# WMC.net
KiCad netlist of a schematic drawn in EAGLE
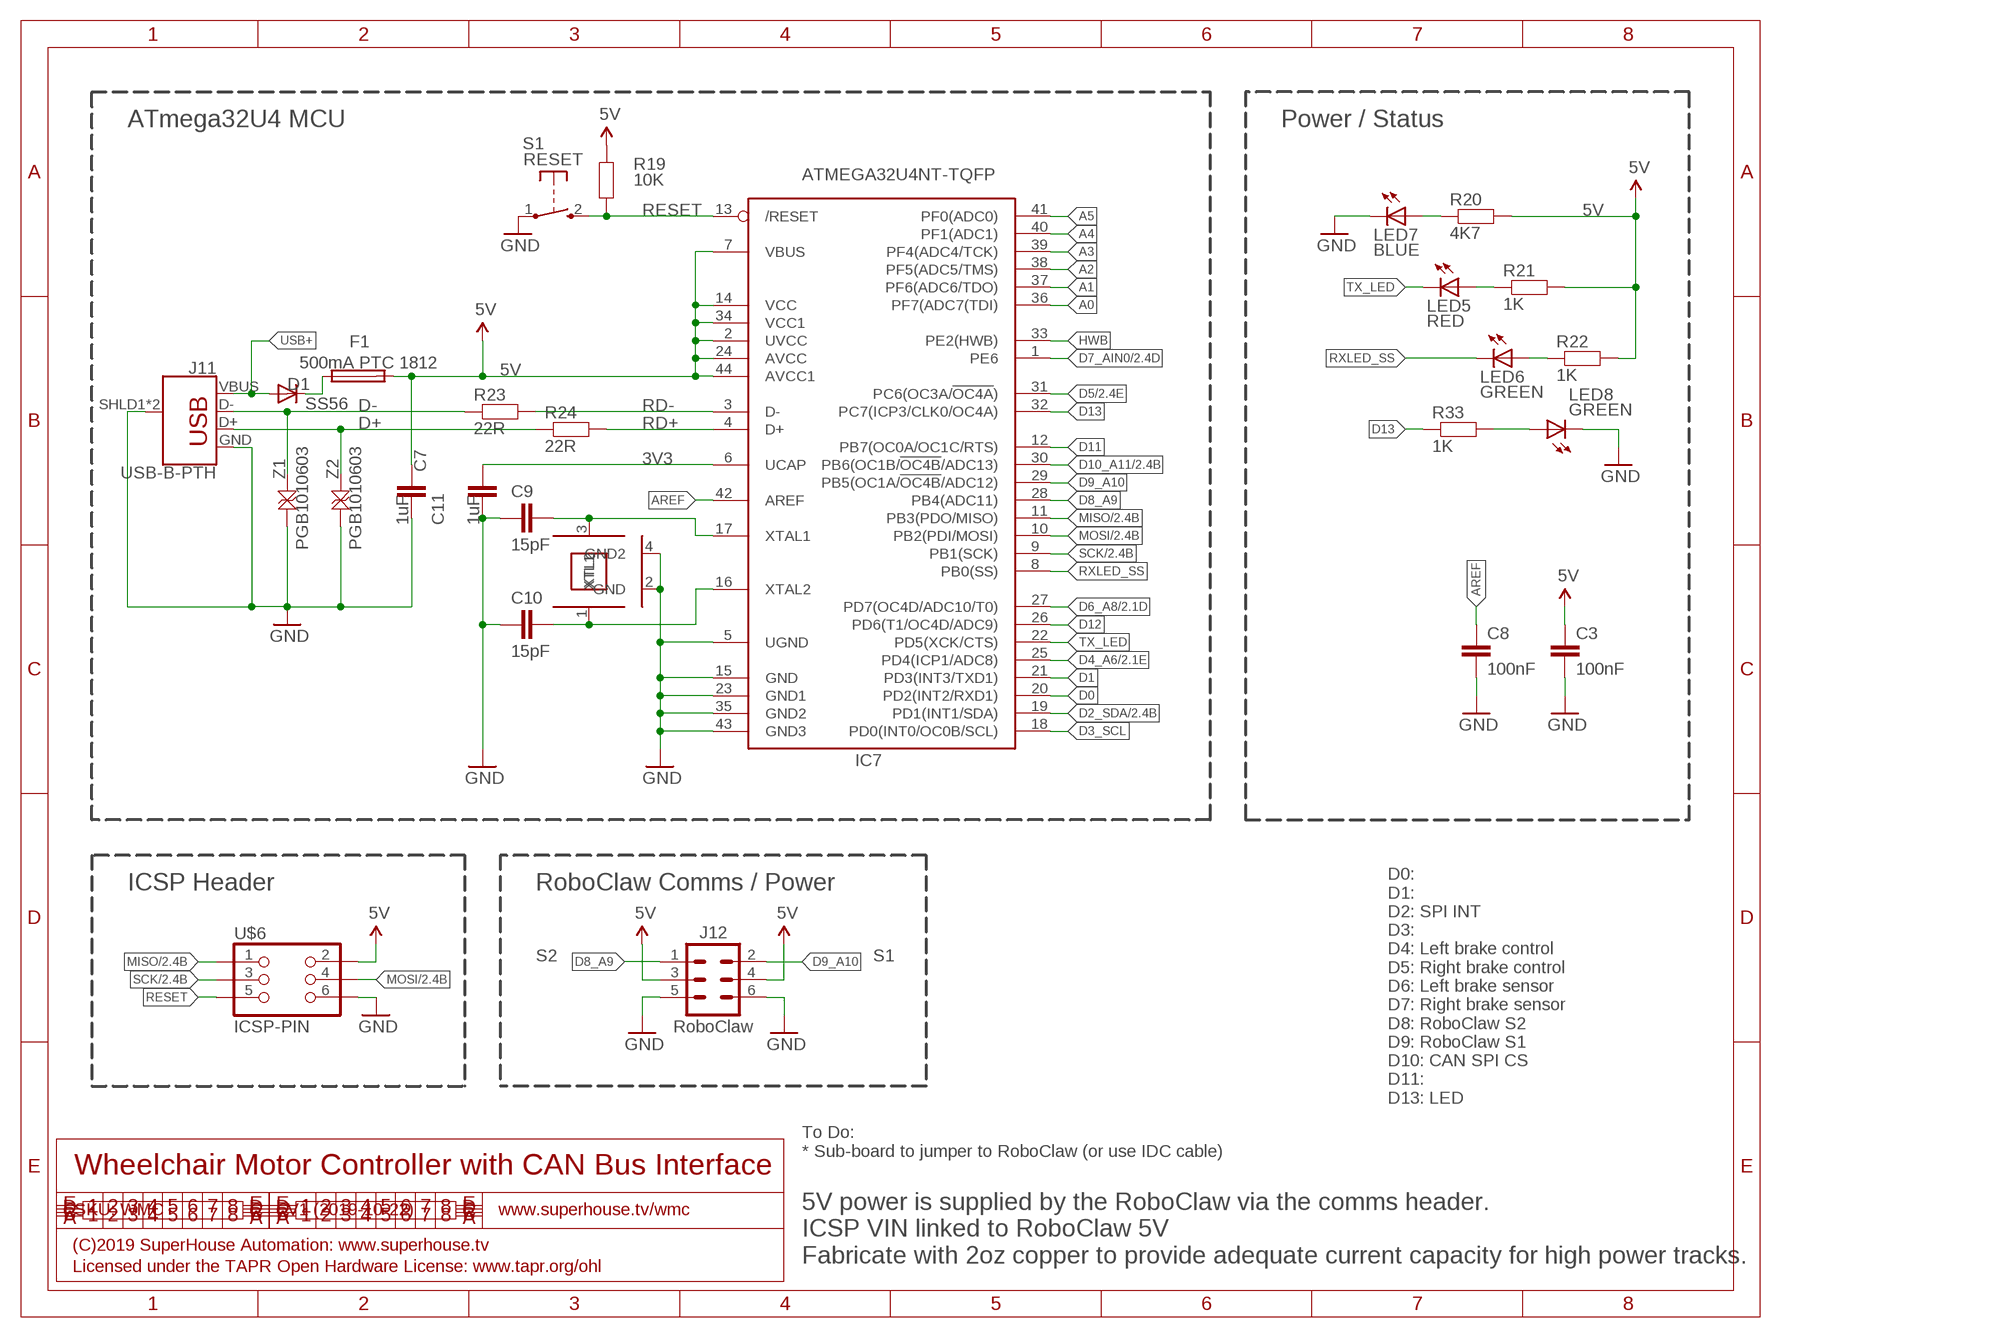
[diagram p0: schematic, sheet 1]
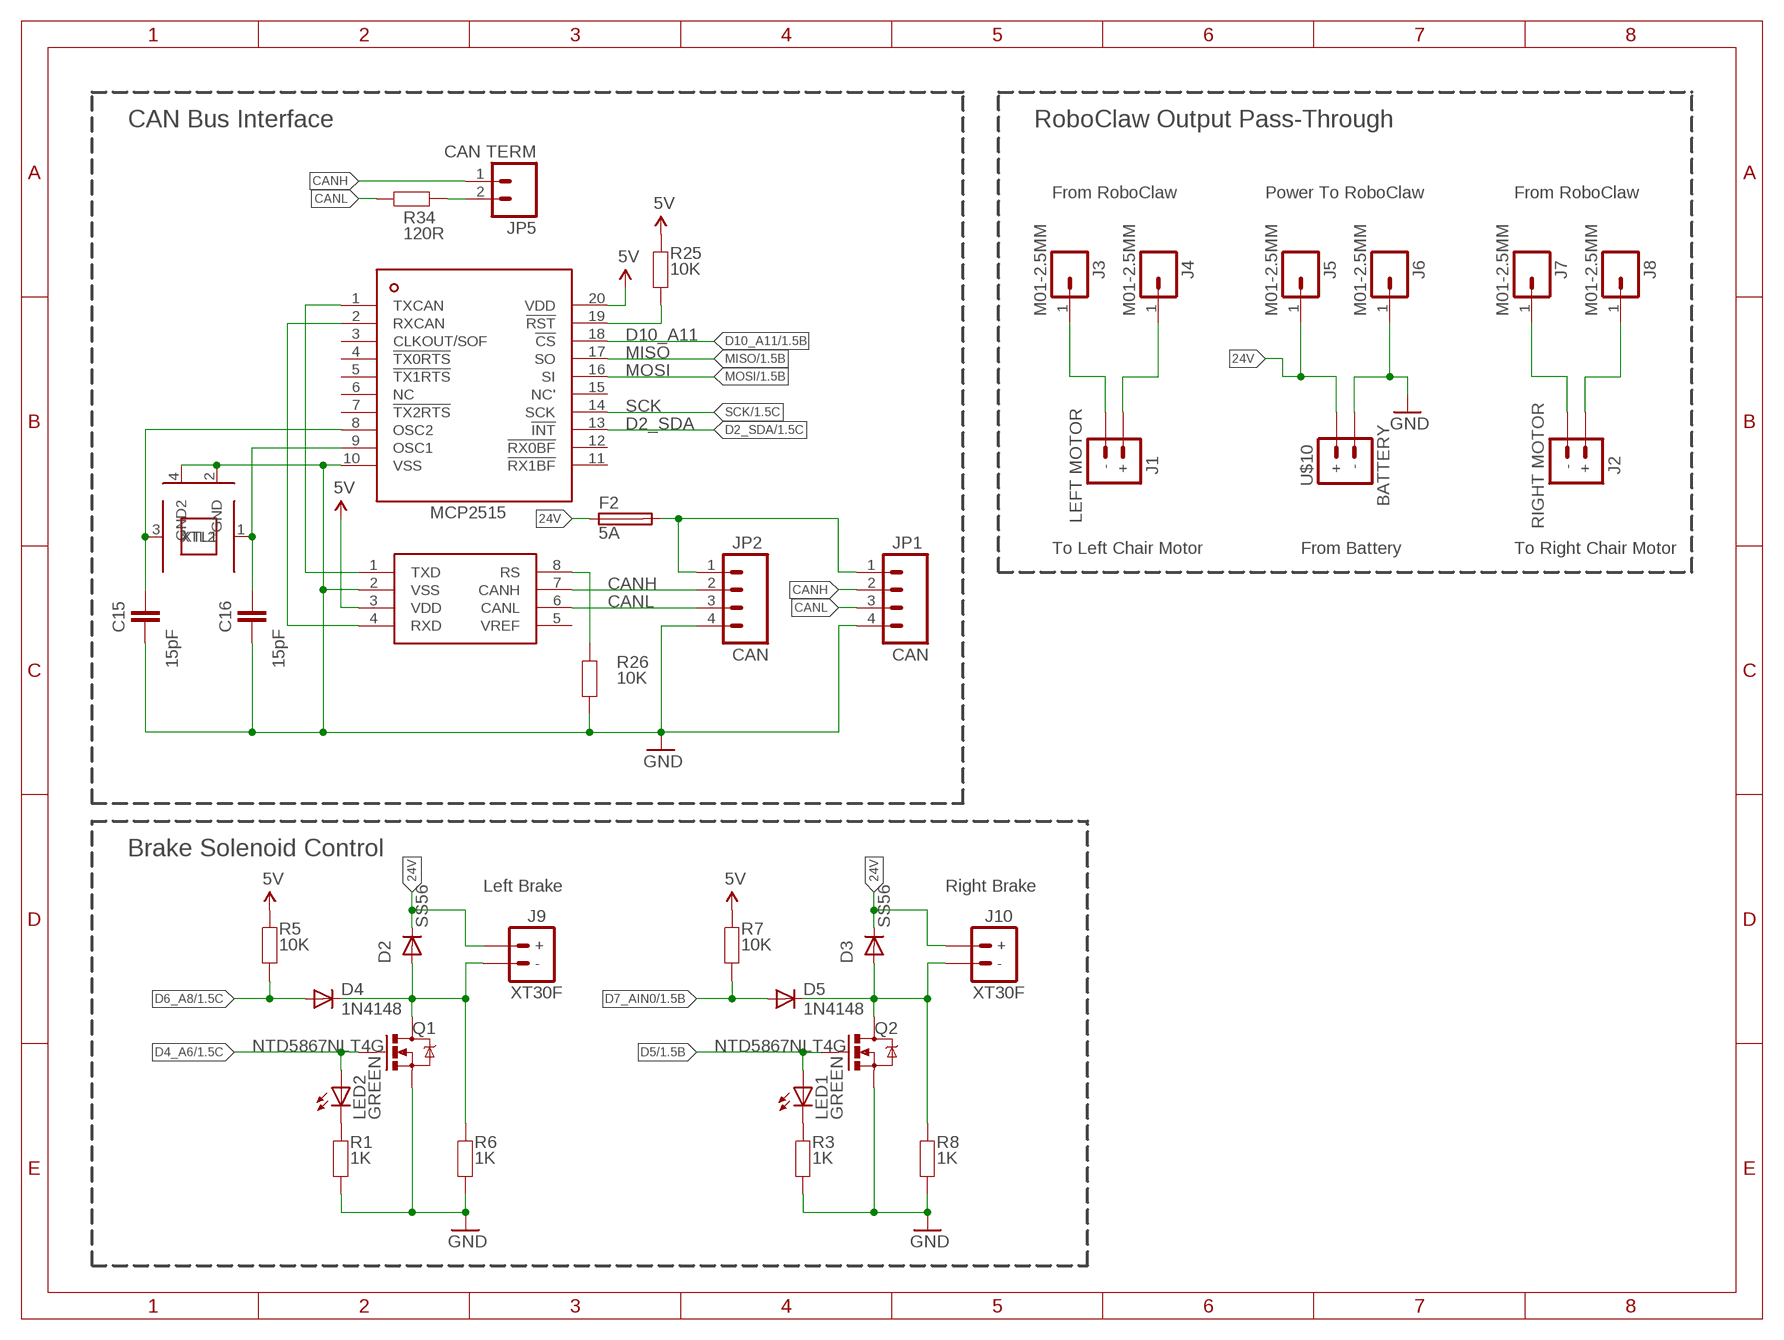
[diagram p1: schematic, sheet 2]

(export (version "E")
  (design (tool "Eeschema 10.0.6"))
  (components
    (comp (ref "C3")
      (value "100nF")
      (footprint "eagle-import:C0603")
      (libsource (lib "eagle-import") (part "CAP0603"))
    )
    (comp (ref "C7")
      (value "1uF")
      (footprint "eagle-import:C0603")
      (libsource (lib "eagle-import") (part "CAP0603"))
    )
    (comp (ref "C8")
      (value "100nF")
      (footprint "eagle-import:C0603")
      (libsource (lib "eagle-import") (part "CAP0603"))
    )
    (comp (ref "C9")
      (value "15pF")
      (footprint "eagle-import:C0603")
      (libsource (lib "eagle-import") (part "CAP0603"))
    )
    (comp (ref "C10")
      (value "15pF")
      (footprint "eagle-import:C0603")
      (libsource (lib "eagle-import") (part "CAP0603"))
    )
    (comp (ref "C11")
      (value "1uF")
      (footprint "eagle-import:C0603")
      (libsource (lib "eagle-import") (part "CAP0603"))
    )
    (comp (ref "D1")
      (value "SS56")
      (footprint "eagle-import:SMA-DIODE")
      (libsource (lib "eagle-import") (part "DIODESMA"))
    )
    (comp (ref "F1")
      (value "500mA PTC 1812")
      (footprint "eagle-import:1812")
      (libsource (lib "eagle-import") (part "PTC050"))
    )
    (comp (ref "IC7")
      (value "ATMEGA32U4NT-TQFP")
      (footprint "eagle-import:TQFP44")
      (libsource (lib "eagle-import") (part "ATMEGA32U4NT-TQFP"))
    )
    (comp (ref "J11")
      (value "USB-B-PTH")
      (footprint "eagle-import:USB-B-PTH")
      (libsource (lib "eagle-import") (part "USB-B-PTH"))
    )
    (comp (ref "J12")
      (value "RoboClaw")
      (footprint "eagle-import:2X03-P")
      (libsource (lib "eagle-import") (part "M02X3-PIN"))
    )
    (comp (ref "LED5")
      (value "RED")
      (footprint "eagle-import:LED-0603")
      (libsource (lib "eagle-import") (part "LED0603"))
    )
    (comp (ref "LED6")
      (value "GREEN")
      (footprint "eagle-import:LED-0603")
      (libsource (lib "eagle-import") (part "LED0603"))
    )
    (comp (ref "LED7")
      (value "BLUE")
      (footprint "eagle-import:LED-0603")
      (libsource (lib "eagle-import") (part "LED0603"))
    )
    (comp (ref "LED8")
      (value "GREEN")
      (footprint "eagle-import:LED-0603")
      (libsource (lib "eagle-import") (part "LED0603"))
    )
    (comp (ref "R19")
      (value "10K")
      (footprint "eagle-import:R0603")
      (libsource (lib "eagle-import") (part "RESISTOR0603"))
    )
    (comp (ref "R20")
      (value "4K7")
      (footprint "eagle-import:R0603")
      (libsource (lib "eagle-import") (part "RESISTOR0603"))
    )
    (comp (ref "R21")
      (value "1K")
      (footprint "eagle-import:R0603")
      (libsource (lib "eagle-import") (part "RESISTOR0603"))
    )
    (comp (ref "R22")
      (value "1K")
      (footprint "eagle-import:R0603")
      (libsource (lib "eagle-import") (part "RESISTOR0603"))
    )
    (comp (ref "R23")
      (value "22R")
      (footprint "eagle-import:R0603")
      (libsource (lib "eagle-import") (part "RESISTOR0603"))
    )
    (comp (ref "R24")
      (value "22R")
      (footprint "eagle-import:R0603")
      (libsource (lib "eagle-import") (part "RESISTOR0603"))
    )
    (comp (ref "R33")
      (value "1K")
      (footprint "eagle-import:R0603")
      (libsource (lib "eagle-import") (part "RESISTOR0603"))
    )
    (comp (ref "S1")
      (value "RESET")
      (footprint "eagle-import:TACTILE_SMT_3X4X2")
      (libsource (lib "eagle-import") (part "TAC_SWITCH_2PINSMT"))
    )
    (comp (ref "U$6")
      (value "ICSP-PIN")
      (footprint "eagle-import:2X03-ICSP")
      (libsource (lib "eagle-import") (part "ICSP-PIN"))
    )
    (comp (ref "XTL2")
      (value "16MHz")
      (footprint "eagle-import:CRYSTAL-SMD-3X2")
      (libsource (lib "eagle-import") (part "CRYSTAL-GND3X2"))
    )
    (comp (ref "Z1")
      (value "PGB1010603")
      (footprint "eagle-import:TVS0603")
      (libsource (lib "eagle-import") (part "TVS0603"))
    )
    (comp (ref "Z2")
      (value "PGB1010603")
      (footprint "eagle-import:TVS0603")
      (libsource (lib "eagle-import") (part "TVS0603"))
    )
    (comp (ref "C15")
      (value "15pF")
      (footprint "eagle-import:C0603")
      (libsource (lib "eagle-import") (part "CAP0603"))
    )
    (comp (ref "C16")
      (value "15pF")
      (footprint "eagle-import:C0603")
      (libsource (lib "eagle-import") (part "CAP0603"))
    )
    (comp (ref "D2")
      (value "SS56")
      (footprint "eagle-import:SMA-DIODE")
      (libsource (lib "eagle-import") (part "DIODESMA"))
    )
    (comp (ref "D3")
      (value "SS56")
      (footprint "eagle-import:SMA-DIODE")
      (libsource (lib "eagle-import") (part "DIODESMA"))
    )
    (comp (ref "D4")
      (value "1N4148")
      (footprint "eagle-import:SOD-323")
      (libsource (lib "eagle-import") (part "DIODESOD"))
    )
    (comp (ref "D5")
      (value "1N4148")
      (footprint "eagle-import:SOD-323")
      (libsource (lib "eagle-import") (part "DIODESOD"))
    )
    (comp (ref "F2")
      (value "5A")
      (footprint "eagle-import:MCCQ-122")
      (libsource (lib "eagle-import") (part "FUSE"))
    )
    (comp (ref "IC5")
      (value "MCP2551")
      (footprint "eagle-import:SO08")
      (libsource (lib "eagle-import") (part "MCP2551"))
    )
    (comp (ref "IC6")
      (value "MCP2515")
      (footprint "eagle-import:TSSOP20")
      (libsource (lib "eagle-import") (part "MCP2515"))
    )
    (comp (ref "J1")
      (value "LEFT MOTOR")
      (footprint "eagle-import:XT60PW-F")
      (libsource (lib "eagle-import") (part "XTXX-60F"))
    )
    (comp (ref "J2")
      (value "RIGHT MOTOR")
      (footprint "eagle-import:XT60PW-F")
      (libsource (lib "eagle-import") (part "XTXX-60F"))
    )
    (comp (ref "J3")
      (value "M01-2.5MM")
      (footprint "eagle-import:1X01-2.5MM")
      (libsource (lib "eagle-import") (part "M01-2.5MM"))
    )
    (comp (ref "J4")
      (value "M01-2.5MM")
      (footprint "eagle-import:1X01-2.5MM")
      (libsource (lib "eagle-import") (part "M01-2.5MM"))
    )
    (comp (ref "J5")
      (value "M01-2.5MM")
      (footprint "eagle-import:1X01-2.5MM")
      (libsource (lib "eagle-import") (part "M01-2.5MM"))
    )
    (comp (ref "J6")
      (value "M01-2.5MM")
      (footprint "eagle-import:1X01-2.5MM")
      (libsource (lib "eagle-import") (part "M01-2.5MM"))
    )
    (comp (ref "J7")
      (value "M01-2.5MM")
      (footprint "eagle-import:1X01-2.5MM")
      (libsource (lib "eagle-import") (part "M01-2.5MM"))
    )
    (comp (ref "J8")
      (value "M01-2.5MM")
      (footprint "eagle-import:1X01-2.5MM")
      (libsource (lib "eagle-import") (part "M01-2.5MM"))
    )
    (comp (ref "J9")
      (value "XT30F")
      (footprint "eagle-import:XT30PW-F")
      (libsource (lib "eagle-import") (part "XTXX-30F"))
    )
    (comp (ref "J10")
      (value "XT30F")
      (footprint "eagle-import:XT30PW-F")
      (libsource (lib "eagle-import") (part "XTXX-30F"))
    )
    (comp (ref "JP1")
      (value "CAN")
      (footprint "eagle-import:1X04-P")
      (libsource (lib "eagle-import") (part "M04-PIN"))
    )
    (comp (ref "JP2")
      (value "CAN")
      (footprint "eagle-import:1X04-P")
      (libsource (lib "eagle-import") (part "M04-PIN"))
    )
    (comp (ref "JP5")
      (value "CAN TERM")
      (footprint "eagle-import:1X02-P")
      (libsource (lib "eagle-import") (part "M02-PIN"))
    )
    (comp (ref "LED1")
      (value "GREEN")
      (footprint "eagle-import:LED-0603")
      (libsource (lib "eagle-import") (part "LED0603"))
    )
    (comp (ref "LED2")
      (value "GREEN")
      (footprint "eagle-import:LED-0603")
      (libsource (lib "eagle-import") (part "LED0603"))
    )
    (comp (ref "Q1")
      (value "NTD5867NLT4G")
      (footprint "eagle-import:DPACK")
      (libsource (lib "eagle-import") (part "MOSFET-NCHANNEL-DPAK"))
    )
    (comp (ref "Q2")
      (value "NTD5867NLT4G")
      (footprint "eagle-import:DPACK")
      (libsource (lib "eagle-import") (part "MOSFET-NCHANNEL-DPAK"))
    )
    (comp (ref "R1")
      (value "1K")
      (footprint "eagle-import:R0603")
      (libsource (lib "eagle-import") (part "RESISTOR0603"))
    )
    (comp (ref "R3")
      (value "1K")
      (footprint "eagle-import:R0603")
      (libsource (lib "eagle-import") (part "RESISTOR0603"))
    )
    (comp (ref "R5")
      (value "10K")
      (footprint "eagle-import:R0603")
      (libsource (lib "eagle-import") (part "RESISTOR0603"))
    )
    (comp (ref "R6")
      (value "1K")
      (footprint "eagle-import:R0603")
      (libsource (lib "eagle-import") (part "RESISTOR0603"))
    )
    (comp (ref "R7")
      (value "10K")
      (footprint "eagle-import:R0603")
      (libsource (lib "eagle-import") (part "RESISTOR0603"))
    )
    (comp (ref "R8")
      (value "1K")
      (footprint "eagle-import:R0603")
      (libsource (lib "eagle-import") (part "RESISTOR0603"))
    )
    (comp (ref "R25")
      (value "10K")
      (footprint "eagle-import:R0603")
      (libsource (lib "eagle-import") (part "RESISTOR0603"))
    )
    (comp (ref "R26")
      (value "10K")
      (footprint "eagle-import:R0603")
      (libsource (lib "eagle-import") (part "RESISTOR0603"))
    )
    (comp (ref "R34")
      (value "120R")
      (footprint "eagle-import:R0603")
      (libsource (lib "eagle-import") (part "RESISTOR0603"))
    )
    (comp (ref "U$10")
      (value "BATTERY")
      (footprint "eagle-import:XT90PW-M")
      (libsource (lib "eagle-import") (part "XTXX-90M"))
    )
    (comp (ref "XTL4")
      (value "16MHz")
      (footprint "eagle-import:CRYSTAL-SMD-3X2")
      (libsource (lib "eagle-import") (part "CRYSTAL-GND3X2"))
    )
  )
  (nets
    (net (code "1") (name "3V3") (class "Default")
      (node (ref "C11") (pin "2") (pinfunction "2_2") (pintype "passive"))
      (node (ref "IC7") (pin "6") (pinfunction "UCAP_6") (pintype "bidirectional"))
    )
    (net (code "2") (name "5V") (class "Default")
      (node (ref "C3") (pin "1") (pinfunction "1_1") (pintype "passive"))
      (node (ref "C7") (pin "1") (pinfunction "1_1") (pintype "passive"))
      (node (ref "F1") (pin "2") (pinfunction "2_2") (pintype "passive"))
      (node (ref "IC5") (pin "3") (pinfunction "VDD_3") (pintype "bidirectional"))
      (node (ref "IC6") (pin "20") (pinfunction "VDD_20") (pintype "bidirectional"))
      (node (ref "IC7") (pin "14") (pinfunction "VCC_14") (pintype "bidirectional"))
      (node (ref "IC7") (pin "2") (pinfunction "UVCC_2") (pintype "bidirectional"))
      (node (ref "IC7") (pin "24") (pinfunction "AVCC_24") (pintype "bidirectional"))
      (node (ref "IC7") (pin "34") (pinfunction "VCC1_34") (pintype "bidirectional"))
      (node (ref "IC7") (pin "44") (pinfunction "AVCC1_44") (pintype "bidirectional"))
      (node (ref "IC7") (pin "7") (pinfunction "VBUS_7") (pintype "bidirectional"))
      (node (ref "J12") (pin "3") (pinfunction "3_3") (pintype "passive"))
      (node (ref "J12") (pin "4") (pinfunction "4_4") (pintype "passive"))
      (node (ref "R19") (pin "2") (pinfunction "2_2") (pintype "passive"))
      (node (ref "R20") (pin "2") (pinfunction "2_2") (pintype "passive"))
      (node (ref "R21") (pin "2") (pinfunction "2_2") (pintype "passive"))
      (node (ref "R22") (pin "2") (pinfunction "2_2") (pintype "passive"))
      (node (ref "R25") (pin "2") (pinfunction "2_2") (pintype "passive"))
      (node (ref "R5") (pin "2") (pinfunction "2_2") (pintype "passive"))
      (node (ref "R7") (pin "2") (pinfunction "2_2") (pintype "passive"))
      (node (ref "U$6") (pin "2") (pinfunction "2_2") (pintype "passive"))
    )
    (net (code "3") (name "24V") (class "Default")
      (node (ref "D2") (pin "C") (pinfunction "C_C") (pintype "passive"))
      (node (ref "D3") (pin "C") (pinfunction "C_C") (pintype "passive"))
      (node (ref "F2") (pin "1") (pinfunction "1_1") (pintype "passive"))
      (node (ref "F2") (pin "2") (pinfunction "1_2") (pintype "passive"))
      (node (ref "J10") (pin "+") (pinfunction "+_+") (pintype "passive"))
      (node (ref "J5") (pin "1") (pinfunction "1_1") (pintype "passive"))
      (node (ref "J9") (pin "+") (pinfunction "+_+") (pintype "passive"))
      (node (ref "U$10") (pin "+") (pinfunction "+_+") (pintype "passive"))
    )
    (net (code "4") (name "A0") (class "Default")
      (node (ref "IC7") (pin "36") (pinfunction "PF7(ADC7(TDI)_36") (pintype "bidirectional"))
    )
    (net (code "5") (name "A1") (class "Default")
      (node (ref "IC7") (pin "37") (pinfunction "PF6(ADC6/TDO)_37") (pintype "bidirectional"))
    )
    (net (code "6") (name "A2") (class "Default")
      (node (ref "IC7") (pin "38") (pinfunction "PF5(ADC5/TMS)_38") (pintype "bidirectional"))
    )
    (net (code "7") (name "A3") (class "Default")
      (node (ref "IC7") (pin "39") (pinfunction "PF4(ADC4/TCK)_39") (pintype "bidirectional"))
    )
    (net (code "8") (name "A4") (class "Default")
      (node (ref "IC7") (pin "40") (pinfunction "PF1(ADC1)_40") (pintype "bidirectional"))
    )
    (net (code "9") (name "A5") (class "Default")
      (node (ref "IC7") (pin "41") (pinfunction "PF0(ADC0)_41") (pintype "bidirectional"))
    )
    (net (code "10") (name "AREF") (class "Default")
      (node (ref "C8") (pin "1") (pinfunction "1_1") (pintype "passive"))
      (node (ref "IC7") (pin "42") (pinfunction "AREF_42") (pintype "bidirectional"))
    )
    (net (code "11") (name "CANH") (class "Default")
      (node (ref "IC5") (pin "7") (pinfunction "CANH_7") (pintype "bidirectional"))
      (node (ref "JP1") (pin "2") (pinfunction "2_2") (pintype "passive"))
      (node (ref "JP2") (pin "2") (pinfunction "2_2") (pintype "passive"))
      (node (ref "JP5") (pin "1") (pinfunction "1_1") (pintype "passive"))
    )
    (net (code "12") (name "CANL") (class "Default")
      (node (ref "IC5") (pin "6") (pinfunction "CANL_6") (pintype "bidirectional"))
      (node (ref "JP1") (pin "3") (pinfunction "3_3") (pintype "passive"))
      (node (ref "JP2") (pin "3") (pinfunction "3_3") (pintype "passive"))
      (node (ref "R34") (pin "1") (pinfunction "1_1") (pintype "passive"))
    )
    (net (code "13") (name "D+") (class "Default")
      (node (ref "J11") (pin "D+") (pinfunction "D+_D+") (pintype "bidirectional"))
      (node (ref "R24") (pin "1") (pinfunction "1_1") (pintype "passive"))
      (node (ref "Z2") (pin "2") (pinfunction "2_2") (pintype "passive"))
    )
    (net (code "14") (name "D-") (class "Default")
      (node (ref "J11") (pin "D-") (pinfunction "D-_D-") (pintype "bidirectional"))
      (node (ref "R23") (pin "1") (pinfunction "1_1") (pintype "passive"))
      (node (ref "Z1") (pin "2") (pinfunction "2_2") (pintype "passive"))
    )
    (net (code "15") (name "D0") (class "Default")
      (node (ref "IC7") (pin "20") (pinfunction "PD2(INT2/RXD1)_20") (pintype "bidirectional"))
    )
    (net (code "16") (name "D1") (class "Default")
      (node (ref "IC7") (pin "21") (pinfunction "PD3(INT3/TXD1)_21") (pintype "bidirectional"))
    )
    (net (code "17") (name "D2_SDA") (class "Default")
      (node (ref "IC6") (pin "13") (pinfunction "~{INT}_13") (pintype "bidirectional"))
      (node (ref "IC7") (pin "19") (pinfunction "PD1(INT1/SDA)_19") (pintype "bidirectional"))
    )
    (net (code "18") (name "D3_SCL") (class "Default")
      (node (ref "IC7") (pin "18") (pinfunction "PD0(INT0/OC0B/SCL)_18") (pintype "bidirectional"))
    )
    (net (code "19") (name "D4_A6") (class "Default")
      (node (ref "IC7") (pin "25") (pinfunction "PD4(ICP1/ADC8)_25") (pintype "bidirectional"))
      (node (ref "LED2") (pin "A") (pinfunction "A_A") (pintype "passive"))
      (node (ref "Q1") (pin "1") (pinfunction "G_1") (pintype "passive"))
    )
    (net (code "20") (name "D5") (class "Default")
      (node (ref "IC7") (pin "31") (pinfunction "PC6(OC3A/~{OC4A})_31") (pintype "bidirectional"))
      (node (ref "LED1") (pin "A") (pinfunction "A_A") (pintype "passive"))
      (node (ref "Q2") (pin "1") (pinfunction "G_1") (pintype "passive"))
    )
    (net (code "21") (name "D6_A8") (class "Default")
      (node (ref "D4") (pin "2") (pinfunction "A_2") (pintype "passive"))
      (node (ref "IC7") (pin "27") (pinfunction "PD7(OC4D/ADC10/T0)_27") (pintype "bidirectional"))
      (node (ref "R5") (pin "1") (pinfunction "1_1") (pintype "passive"))
    )
    (net (code "22") (name "D7_AIN0") (class "Default")
      (node (ref "D5") (pin "2") (pinfunction "A_2") (pintype "passive"))
      (node (ref "IC7") (pin "1") (pinfunction "PE6_1") (pintype "bidirectional"))
      (node (ref "R7") (pin "1") (pinfunction "1_1") (pintype "passive"))
    )
    (net (code "23") (name "D8_A9") (class "Default")
      (node (ref "IC7") (pin "28") (pinfunction "PB4(ADC11)_28") (pintype "bidirectional"))
      (node (ref "J12") (pin "1") (pinfunction "1_1") (pintype "passive"))
    )
    (net (code "24") (name "D9_A10") (class "Default")
      (node (ref "IC7") (pin "29") (pinfunction "PB5(OC1A/~{OC4B}/ADC12)_29") (pintype "bidirectional"))
      (node (ref "J12") (pin "2") (pinfunction "2_2") (pintype "passive"))
    )
    (net (code "25") (name "D10_A11") (class "Default")
      (node (ref "IC6") (pin "18") (pinfunction "~{CS}_18") (pintype "bidirectional"))
      (node (ref "IC7") (pin "30") (pinfunction "PB6(OC1B/~{OC4B}/ADC13)_30") (pintype "bidirectional"))
    )
    (net (code "26") (name "D11") (class "Default")
      (node (ref "IC7") (pin "12") (pinfunction "PB7(OC0A/OC1C/RTS)_12") (pintype "bidirectional"))
    )
    (net (code "27") (name "D12") (class "Default")
      (node (ref "IC7") (pin "26") (pinfunction "PD6(T1/OC4D/ADC9)_26") (pintype "bidirectional"))
    )
    (net (code "28") (name "D13") (class "Default")
      (node (ref "IC7") (pin "32") (pinfunction "PC7(ICP3/CLK0/OC4A)_32") (pintype "bidirectional"))
      (node (ref "R33") (pin "1") (pinfunction "1_1") (pintype "passive"))
    )
    (net (code "29") (name "GND") (class "Default")
      (node (ref "C10") (pin "1") (pinfunction "1_1") (pintype "passive"))
      (node (ref "C11") (pin "1") (pinfunction "1_1") (pintype "passive"))
      (node (ref "C15") (pin "1") (pinfunction "1_1") (pintype "passive"))
      (node (ref "C16") (pin "1") (pinfunction "1_1") (pintype "passive"))
      (node (ref "C3") (pin "2") (pinfunction "2_2") (pintype "passive"))
      (node (ref "C7") (pin "2") (pinfunction "2_2") (pintype "passive"))
      (node (ref "C8") (pin "2") (pinfunction "2_2") (pintype "passive"))
      (node (ref "C9") (pin "1") (pinfunction "1_1") (pintype "passive"))
      (node (ref "IC5") (pin "2") (pinfunction "VSS_2") (pintype "bidirectional"))
      (node (ref "IC6") (pin "10") (pinfunction "VSS_10") (pintype "bidirectional"))
      (node (ref "IC7") (pin "15") (pinfunction "GND_15") (pintype "bidirectional"))
      (node (ref "IC7") (pin "23") (pinfunction "GND1_23") (pintype "bidirectional"))
      (node (ref "IC7") (pin "35") (pinfunction "GND2_35") (pintype "bidirectional"))
      (node (ref "IC7") (pin "43") (pinfunction "GND3_43") (pintype "bidirectional"))
      (node (ref "IC7") (pin "5") (pinfunction "UGND_5") (pintype "bidirectional"))
      (node (ref "J11") (pin "GND") (pinfunction "GND_GND") (pintype "power_in"))
      (node (ref "J11") (pin "SHLD1") (pinfunction "SHIELD_SHLD1") (pintype "bidirectional"))
      (node (ref "J11") (pin "SHLD2") (pinfunction "SHIELD_SHLD2") (pintype "bidirectional"))
      (node (ref "J12") (pin "5") (pinfunction "5_5") (pintype "passive"))
      (node (ref "J12") (pin "6") (pinfunction "6_6") (pintype "passive"))
      (node (ref "J6") (pin "1") (pinfunction "1_1") (pintype "passive"))
      (node (ref "JP1") (pin "4") (pinfunction "4_4") (pintype "passive"))
      (node (ref "JP2") (pin "4") (pinfunction "4_4") (pintype "passive"))
      (node (ref "LED7") (pin "C") (pinfunction "C_C") (pintype "passive"))
      (node (ref "LED8") (pin "C") (pinfunction "C_C") (pintype "passive"))
      (node (ref "Q1") (pin "3") (pinfunction "S_3") (pintype "passive"))
      (node (ref "Q2") (pin "3") (pinfunction "S_3") (pintype "passive"))
      (node (ref "R1") (pin "1") (pinfunction "1_1") (pintype "passive"))
      (node (ref "R26") (pin "1") (pinfunction "1_1") (pintype "passive"))
      (node (ref "R3") (pin "1") (pinfunction "1_1") (pintype "passive"))
      (node (ref "R6") (pin "1") (pinfunction "1_1") (pintype "passive"))
      (node (ref "R8") (pin "1") (pinfunction "1_1") (pintype "passive"))
      (node (ref "S1") (pin "1") (pinfunction "P_1") (pintype "passive"))
      (node (ref "U$10") (pin "-") (pinfunction "-_-") (pintype "passive"))
      (node (ref "U$6") (pin "6") (pinfunction "6_6") (pintype "passive"))
      (node (ref "XTL2") (pin "2") (pinfunction "GND_2") (pintype "bidirectional"))
      (node (ref "XTL2") (pin "4") (pinfunction "GND2_4") (pintype "bidirectional"))
      (node (ref "XTL4") (pin "2") (pinfunction "GND_2") (pintype "bidirectional"))
      (node (ref "XTL4") (pin "4") (pinfunction "GND2_4") (pintype "bidirectional"))
      (node (ref "Z1") (pin "1") (pinfunction "1_1") (pintype "passive"))
      (node (ref "Z2") (pin "1") (pinfunction "1_1") (pintype "passive"))
    )
    (net (code "30") (name "HWB") (class "Default")
      (node (ref "IC7") (pin "33") (pinfunction "PE2(HWB)_33") (pintype "bidirectional"))
    )
    (net (code "31") (name "MISO") (class "Default")
      (node (ref "IC6") (pin "17") (pinfunction "SO_17") (pintype "bidirectional"))
      (node (ref "IC7") (pin "11") (pinfunction "PB3(PDO/MISO)_11") (pintype "bidirectional"))
      (node (ref "U$6") (pin "1") (pinfunction "1_1") (pintype "passive"))
    )
    (net (code "32") (name "MOSI") (class "Default")
      (node (ref "IC6") (pin "16") (pinfunction "SI_16") (pintype "bidirectional"))
      (node (ref "IC7") (pin "10") (pinfunction "PB2(PDI/MOSI)_10") (pintype "bidirectional"))
      (node (ref "U$6") (pin "4") (pinfunction "4_4") (pintype "passive"))
    )
    (net (code "33") (name "Net-(D1-PadC)") (class "Default")
      (node (ref "D1") (pin "C") (pinfunction "C_C") (pintype "passive"))
      (node (ref "F1") (pin "1") (pinfunction "1_1") (pintype "passive"))
    )
    (net (code "34") (name "Net-(D4-C)") (class "Default")
      (node (ref "D2") (pin "A") (pinfunction "A_A") (pintype "passive"))
      (node (ref "D4") (pin "1") (pinfunction "C_1") (pintype "passive"))
      (node (ref "J9") (pin "-") (pinfunction "-_-") (pintype "passive"))
      (node (ref "Q1") (pin "2") (pinfunction "D_2") (pintype "passive"))
      (node (ref "R6") (pin "2") (pinfunction "2_2") (pintype "passive"))
    )
    (net (code "35") (name "Net-(D5-C)") (class "Default")
      (node (ref "D3") (pin "A") (pinfunction "A_A") (pintype "passive"))
      (node (ref "D5") (pin "1") (pinfunction "C_1") (pintype "passive"))
      (node (ref "J10") (pin "-") (pinfunction "-_-") (pintype "passive"))
      (node (ref "Q2") (pin "2") (pinfunction "D_2") (pintype "passive"))
      (node (ref "R8") (pin "2") (pinfunction "2_2") (pintype "passive"))
    )
    (net (code "36") (name "Net-(F2-2-Pad3)") (class "Default")
      (node (ref "F2") (pin "3") (pinfunction "2_3") (pintype "passive"))
      (node (ref "F2") (pin "4") (pinfunction "2_4") (pintype "passive"))
      (node (ref "JP1") (pin "1") (pinfunction "1_1") (pintype "passive"))
      (node (ref "JP2") (pin "1") (pinfunction "1_1") (pintype "passive"))
    )
    (net (code "37") (name "Net-(IC5-RS)") (class "Default")
      (node (ref "IC5") (pin "8") (pinfunction "RS_8") (pintype "bidirectional"))
      (node (ref "R26") (pin "2") (pinfunction "2_2") (pintype "passive"))
    )
    (net (code "38") (name "Net-(IC5-RXD)") (class "Default")
      (node (ref "IC5") (pin "4") (pinfunction "RXD_4") (pintype "bidirectional"))
      (node (ref "IC6") (pin "2") (pinfunction "RXCAN_2") (pintype "bidirectional"))
    )
    (net (code "39") (name "Net-(IC5-TXD)") (class "Default")
      (node (ref "IC5") (pin "1") (pinfunction "TXD_1") (pintype "bidirectional"))
      (node (ref "IC6") (pin "1") (pinfunction "TXCAN_1") (pintype "bidirectional"))
    )
    (net (code "40") (name "Net-(IC6-OSC1)") (class "Default")
      (node (ref "C16") (pin "2") (pinfunction "2_2") (pintype "passive"))
      (node (ref "IC6") (pin "9") (pinfunction "OSC1_9") (pintype "bidirectional"))
      (node (ref "XTL4") (pin "1") (pinfunction "XTL1_1") (pintype "bidirectional"))
    )
    (net (code "41") (name "Net-(IC6-OSC2)") (class "Default")
      (node (ref "C15") (pin "2") (pinfunction "2_2") (pintype "passive"))
      (node (ref "IC6") (pin "8") (pinfunction "OSC2_8") (pintype "bidirectional"))
      (node (ref "XTL4") (pin "3") (pinfunction "XTL2_3") (pintype "bidirectional"))
    )
    (net (code "42") (name "Net-(IC6-~{RST})") (class "Default")
      (node (ref "IC6") (pin "19") (pinfunction "~{RST}_19") (pintype "bidirectional"))
      (node (ref "R25") (pin "1") (pinfunction "1_1") (pintype "passive"))
    )
    (net (code "43") (name "Net-(IC7-XTAL1)") (class "Default")
      (node (ref "C9") (pin "2") (pinfunction "2_2") (pintype "passive"))
      (node (ref "IC7") (pin "17") (pinfunction "XTAL1_17") (pintype "bidirectional"))
      (node (ref "XTL2") (pin "3") (pinfunction "XTL2_3") (pintype "bidirectional"))
    )
    (net (code "44") (name "Net-(IC7-XTAL2)") (class "Default")
      (node (ref "C10") (pin "2") (pinfunction "2_2") (pintype "passive"))
      (node (ref "IC7") (pin "16") (pinfunction "XTAL2_16") (pintype "bidirectional"))
      (node (ref "XTL2") (pin "1") (pinfunction "XTL1_1") (pintype "bidirectional"))
    )
    (net (code "45") (name "Net-(J1-Pad+)") (class "Default")
      (node (ref "J1") (pin "+") (pinfunction "+_+") (pintype "passive"))
      (node (ref "J4") (pin "1") (pinfunction "1_1") (pintype "passive"))
    )
    (net (code "46") (name "Net-(J1-Pad-)") (class "Default")
      (node (ref "J1") (pin "-") (pinfunction "-_-") (pintype "passive"))
      (node (ref "J3") (pin "1") (pinfunction "1_1") (pintype "passive"))
    )
    (net (code "47") (name "Net-(J2-Pad+)") (class "Default")
      (node (ref "J2") (pin "+") (pinfunction "+_+") (pintype "passive"))
      (node (ref "J8") (pin "1") (pinfunction "1_1") (pintype "passive"))
    )
    (net (code "48") (name "Net-(J2-Pad-)") (class "Default")
      (node (ref "J2") (pin "-") (pinfunction "-_-") (pintype "passive"))
      (node (ref "J7") (pin "1") (pinfunction "1_1") (pintype "passive"))
    )
    (net (code "49") (name "Net-(JP5-Pad2)") (class "Default")
      (node (ref "JP5") (pin "2") (pinfunction "2_2") (pintype "passive"))
      (node (ref "R34") (pin "2") (pinfunction "2_2") (pintype "passive"))
    )
    (net (code "50") (name "Net-(LED1-PadC)") (class "Default")
      (node (ref "LED1") (pin "C") (pinfunction "C_C") (pintype "passive"))
      (node (ref "R3") (pin "2") (pinfunction "2_2") (pintype "passive"))
    )
    (net (code "51") (name "Net-(LED2-PadC)") (class "Default")
      (node (ref "LED2") (pin "C") (pinfunction "C_C") (pintype "passive"))
      (node (ref "R1") (pin "2") (pinfunction "2_2") (pintype "passive"))
    )
    (net (code "52") (name "Net-(LED5-PadA)") (class "Default")
      (node (ref "LED5") (pin "A") (pinfunction "A_A") (pintype "passive"))
      (node (ref "R21") (pin "1") (pinfunction "1_1") (pintype "passive"))
    )
    (net (code "53") (name "Net-(LED6-PadA)") (class "Default")
      (node (ref "LED6") (pin "A") (pinfunction "A_A") (pintype "passive"))
      (node (ref "R22") (pin "1") (pinfunction "1_1") (pintype "passive"))
    )
    (net (code "54") (name "Net-(LED7-PadA)") (class "Default")
      (node (ref "LED7") (pin "A") (pinfunction "A_A") (pintype "passive"))
      (node (ref "R20") (pin "1") (pinfunction "1_1") (pintype "passive"))
    )
    (net (code "55") (name "Net-(LED8-PadA)") (class "Default")
      (node (ref "LED8") (pin "A") (pinfunction "A_A") (pintype "passive"))
      (node (ref "R33") (pin "2") (pinfunction "2_2") (pintype "passive"))
    )
    (net (code "56") (name "RD+") (class "Default")
      (node (ref "IC7") (pin "4") (pinfunction "D+_4") (pintype "bidirectional"))
      (node (ref "R24") (pin "2") (pinfunction "2_2") (pintype "passive"))
    )
    (net (code "57") (name "RD-") (class "Default")
      (node (ref "IC7") (pin "3") (pinfunction "D-_3") (pintype "bidirectional"))
      (node (ref "R23") (pin "2") (pinfunction "2_2") (pintype "passive"))
    )
    (net (code "58") (name "RESET") (class "Default")
      (node (ref "IC7") (pin "13") (pinfunction "/RESET_13") (pintype "bidirectional"))
      (node (ref "R19") (pin "1") (pinfunction "1_1") (pintype "passive"))
      (node (ref "S1") (pin "2") (pinfunction "S_2") (pintype "passive"))
      (node (ref "U$6") (pin "5") (pinfunction "5_5") (pintype "passive"))
    )
    (net (code "59") (name "RXLED_SS") (class "Default")
      (node (ref "IC7") (pin "8") (pinfunction "PB0(SS)_8") (pintype "bidirectional"))
      (node (ref "LED6") (pin "C") (pinfunction "C_C") (pintype "passive"))
    )
    (net (code "60") (name "SCK") (class "Default")
      (node (ref "IC6") (pin "14") (pinfunction "SCK_14") (pintype "bidirectional"))
      (node (ref "IC7") (pin "9") (pinfunction "PB1(SCK)_9") (pintype "bidirectional"))
      (node (ref "U$6") (pin "3") (pinfunction "3_3") (pintype "passive"))
    )
    (net (code "61") (name "TX_LED") (class "Default")
      (node (ref "IC7") (pin "22") (pinfunction "PD5(XCK/CTS)_22") (pintype "bidirectional"))
      (node (ref "LED5") (pin "C") (pinfunction "C_C") (pintype "passive"))
    )
    (net (code "62") (name "USB+") (class "Default")
      (node (ref "D1") (pin "A") (pinfunction "A_A") (pintype "passive"))
      (node (ref "J11") (pin "VBUS") (pinfunction "VBUS_VBUS") (pintype "power_in"))
    )
    (net (code "63") (name "unconnected-(IC5-VREF-Pad5)") (class "Default")
      (node (ref "IC5") (pin "5") (pinfunction "VREF_5") (pintype "bidirectional"))
    )
    (net (code "64") (name "unconnected-(IC6-CLKOUT{slash}SOF-Pad3)") (class "Default")
      (node (ref "IC6") (pin "3") (pinfunction "CLKOUT/SOF_3") (pintype "bidirectional"))
    )
    (net (code "65") (name "unconnected-(IC6-NC'-Pad15)") (class "Default")
      (node (ref "IC6") (pin "15") (pinfunction "NC'_15") (pintype "bidirectional"))
    )
    (net (code "66") (name "unconnected-(IC6-NC-Pad6)") (class "Default")
      (node (ref "IC6") (pin "6") (pinfunction "NC_6") (pintype "bidirectional"))
    )
    (net (code "67") (name "unconnected-(IC6-~{RX0BF}-Pad12)") (class "Default")
      (node (ref "IC6") (pin "12") (pinfunction "~{RX0BF}_12") (pintype "bidirectional"))
    )
    (net (code "68") (name "unconnected-(IC6-~{RX1BF}-Pad11)") (class "Default")
      (node (ref "IC6") (pin "11") (pinfunction "~{RX1BF}_11") (pintype "bidirectional"))
    )
    (net (code "69") (name "unconnected-(IC6-~{TX0RTS}-Pad4)") (class "Default")
      (node (ref "IC6") (pin "4") (pinfunction "~{TX0RTS}_4") (pintype "bidirectional"))
    )
    (net (code "70") (name "unconnected-(IC6-~{TX1RTS}-Pad5)") (class "Default")
      (node (ref "IC6") (pin "5") (pinfunction "~{TX1RTS}_5") (pintype "bidirectional"))
    )
    (net (code "71") (name "unconnected-(IC6-~{TX2RTS}-Pad7)") (class "Default")
      (node (ref "IC6") (pin "7") (pinfunction "~{TX2RTS}_7") (pintype "bidirectional"))
    )
  )
)
